# SCH_pipicoshield_2023-05-22.net
KiCad netlist of a schematic drawn in EasyEDA
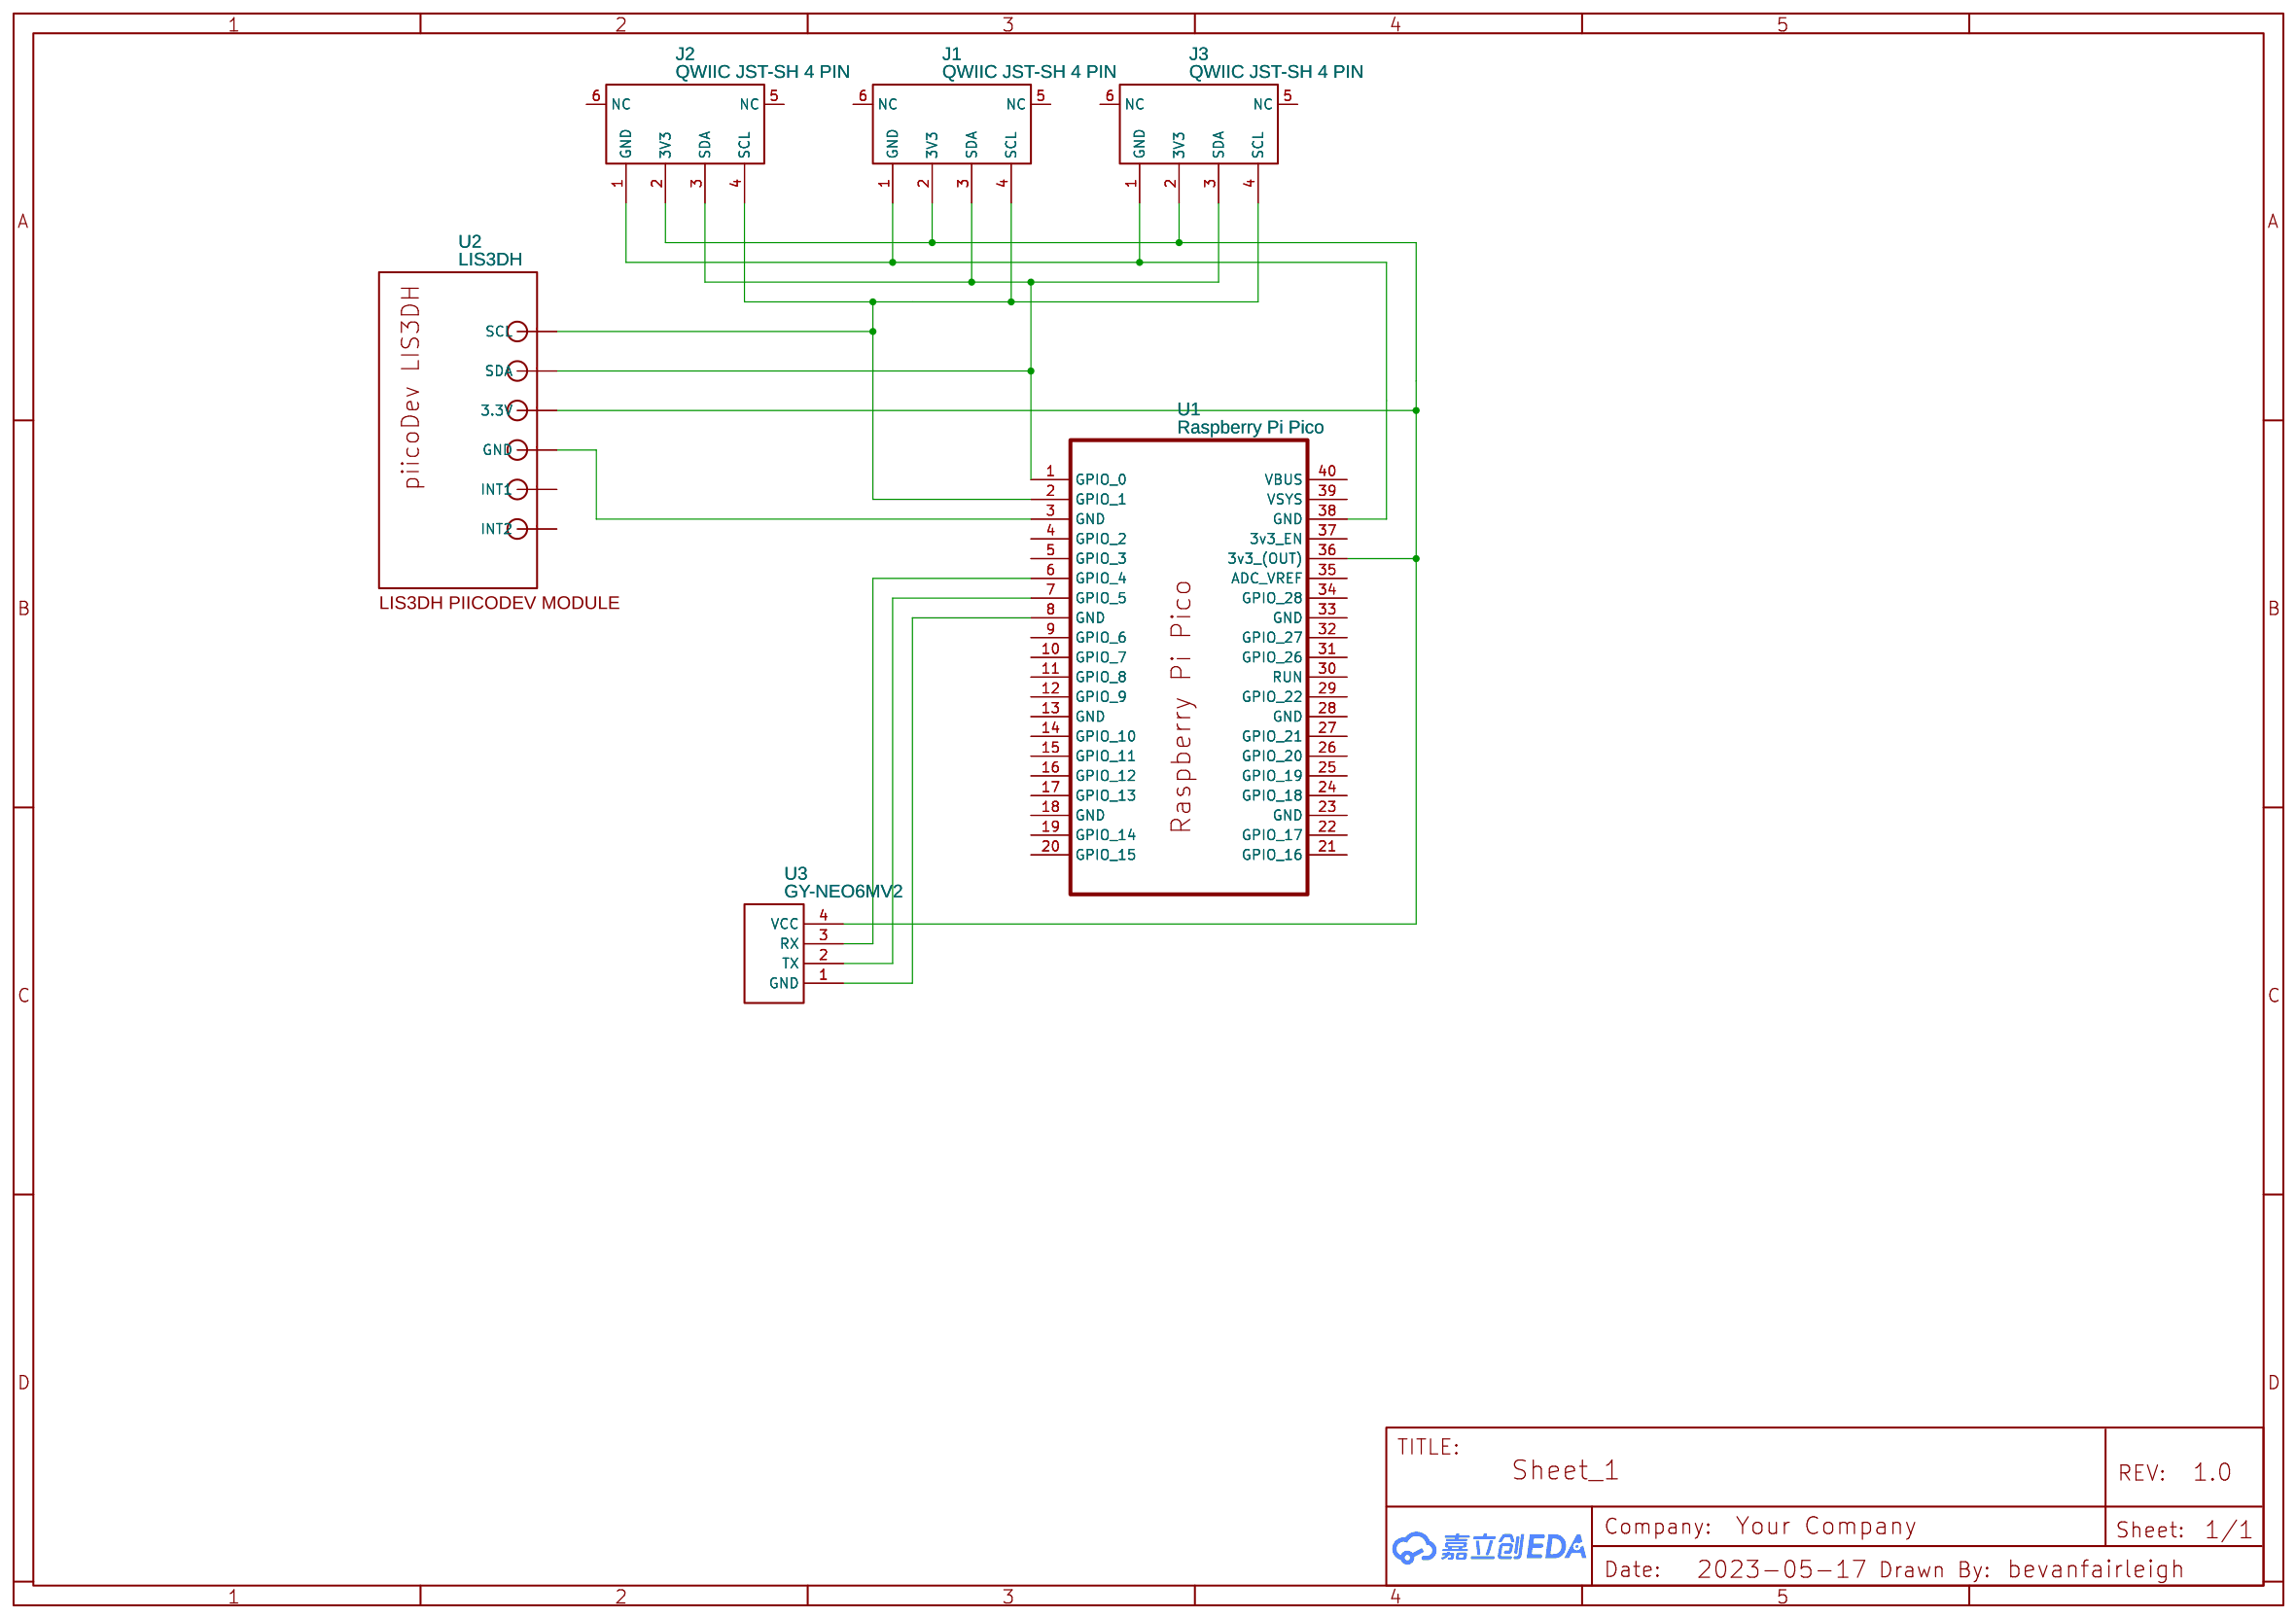
[diagram p0: schematic sheet]

(export (version "E")
  (design (tool "Eeschema 10.0.6"))
  (components
    (comp (ref "J1") (value "QWIIC JST-SH 4 PIN") (libsource (lib "") (part "QWIIC JST-SH 4 PIN")))
    (comp (ref "J2") (value "QWIIC JST-SH 4 PIN") (libsource (lib "") (part "QWIIC JST-SH 4 PIN")))
    (comp (ref "J3") (value "QWIIC JST-SH 4 PIN") (libsource (lib "") (part "QWIIC JST-SH 4 PIN")))
    (comp (ref "U1") (value "Raspberry Pi Pico") (libsource (lib "") (part "Raspberry Pi Pico W")))
    (comp (ref "U2") (value "LIS3DH") (libsource (lib "") (part "BME280")))
    (comp (ref "U3") (value "GY-NEO6MV2") (libsource (lib "") (part "GY-NEO6MV2")))
  )
  (nets
    (net (code "1") (name "Net-(J1-3V3)") (class "Default")
      (node (ref "J1") (pin "2") (pinfunction "3V3_2") (pintype "passive"))
      (node (ref "J2") (pin "2") (pinfunction "3V3_2") (pintype "passive"))
      (node (ref "J3") (pin "2") (pinfunction "3V3_2") (pintype "passive"))
      (node (ref "U1") (pin "36") (pinfunction "3v3_(OUT)_36") (pintype "unspecified"))
      (node (ref "U2") (pin "4") (pinfunction "3.3V_4") (pintype "unspecified"))
      (node (ref "U3") (pin "4") (pinfunction "VCC_4") (pintype "passive"))
    )
    (net (code "2") (name "Net-(J1-GND)") (class "Default")
      (node (ref "J1") (pin "1") (pinfunction "GND_1") (pintype "passive"))
      (node (ref "J2") (pin "1") (pinfunction "GND_1") (pintype "passive"))
      (node (ref "J3") (pin "1") (pinfunction "GND_1") (pintype "passive"))
      (node (ref "U1") (pin "38") (pinfunction "GND_38") (pintype "unspecified"))
    )
    (net (code "3") (name "Net-(J1-SCL)") (class "Default")
      (node (ref "J1") (pin "4") (pinfunction "SCL_4") (pintype "bidirectional"))
      (node (ref "J2") (pin "4") (pinfunction "SCL_4") (pintype "bidirectional"))
      (node (ref "J3") (pin "4") (pinfunction "SCL_4") (pintype "bidirectional"))
      (node (ref "U1") (pin "2") (pinfunction "GPIO_1_2") (pintype "unspecified"))
      (node (ref "U2") (pin "6") (pinfunction "SCL_6") (pintype "unspecified"))
    )
    (net (code "4") (name "Net-(J1-SDA)") (class "Default")
      (node (ref "J1") (pin "3") (pinfunction "SDA_3") (pintype "bidirectional"))
      (node (ref "J2") (pin "3") (pinfunction "SDA_3") (pintype "bidirectional"))
      (node (ref "J3") (pin "3") (pinfunction "SDA_3") (pintype "bidirectional"))
      (node (ref "U1") (pin "1") (pinfunction "GPIO_0_1") (pintype "unspecified"))
      (node (ref "U2") (pin "5") (pinfunction "SDA_5") (pintype "unspecified"))
    )
    (net (code "5") (name "Net-(U1-GPIO_4)") (class "Default")
      (node (ref "U1") (pin "6") (pinfunction "GPIO_4_6") (pintype "unspecified"))
      (node (ref "U3") (pin "3") (pinfunction "RX_3") (pintype "input"))
    )
    (net (code "6") (name "Net-(U1-GPIO_5)") (class "Default")
      (node (ref "U1") (pin "7") (pinfunction "GPIO_5_7") (pintype "unspecified"))
      (node (ref "U3") (pin "2") (pinfunction "TX_2") (pintype "output"))
    )
    (net (code "7") (name "Net-(U2-GND)") (class "Default")
      (node (ref "U1") (pin "3") (pinfunction "GND_3") (pintype "unspecified"))
      (node (ref "U2") (pin "3") (pinfunction "GND_3") (pintype "unspecified"))
    )
    (net (code "8") (name "Net-(U3-GND)") (class "Default")
      (node (ref "U1") (pin "8") (pinfunction "GND_8") (pintype "unspecified"))
      (node (ref "U3") (pin "1") (pinfunction "GND_1") (pintype "passive"))
    )
    (net (code "9") (name "unconnected-(J1-NC-Pad5)") (class "Default")
      (node (ref "J1") (pin "5") (pinfunction "NC_5") (pintype "unspecified"))
    )
    (net (code "10") (name "unconnected-(J1-NC-Pad6)") (class "Default")
      (node (ref "J1") (pin "6") (pinfunction "NC_6") (pintype "unspecified"))
    )
    (net (code "11") (name "unconnected-(J2-NC-Pad5)") (class "Default")
      (node (ref "J2") (pin "5") (pinfunction "NC_5") (pintype "unspecified"))
    )
    (net (code "12") (name "unconnected-(J2-NC-Pad6)") (class "Default")
      (node (ref "J2") (pin "6") (pinfunction "NC_6") (pintype "unspecified"))
    )
    (net (code "13") (name "unconnected-(J3-NC-Pad5)") (class "Default")
      (node (ref "J3") (pin "5") (pinfunction "NC_5") (pintype "unspecified"))
    )
    (net (code "14") (name "unconnected-(J3-NC-Pad6)") (class "Default")
      (node (ref "J3") (pin "6") (pinfunction "NC_6") (pintype "unspecified"))
    )
    (net (code "15") (name "unconnected-(U1-3v3_EN-Pad37)") (class "Default")
      (node (ref "U1") (pin "37") (pinfunction "3v3_EN_37") (pintype "unspecified"))
    )
    (net (code "16") (name "unconnected-(U1-ADC_VREF-Pad35)") (class "Default")
      (node (ref "U1") (pin "35") (pinfunction "ADC_VREF_35") (pintype "unspecified"))
    )
    (net (code "17") (name "unconnected-(U1-GND-Pad13)") (class "Default")
      (node (ref "U1") (pin "13") (pinfunction "GND_13") (pintype "unspecified"))
    )
    (net (code "18") (name "unconnected-(U1-GND-Pad18)") (class "Default")
      (node (ref "U1") (pin "18") (pinfunction "GND_18") (pintype "unspecified"))
    )
    (net (code "19") (name "unconnected-(U1-GND-Pad23)") (class "Default")
      (node (ref "U1") (pin "23") (pinfunction "GND_23") (pintype "unspecified"))
    )
    (net (code "20") (name "unconnected-(U1-GND-Pad28)") (class "Default")
      (node (ref "U1") (pin "28") (pinfunction "GND_28") (pintype "unspecified"))
    )
    (net (code "21") (name "unconnected-(U1-GND-Pad33)") (class "Default")
      (node (ref "U1") (pin "33") (pinfunction "GND_33") (pintype "unspecified"))
    )
    (net (code "22") (name "unconnected-(U1-GPIO_2-Pad4)") (class "Default")
      (node (ref "U1") (pin "4") (pinfunction "GPIO_2_4") (pintype "unspecified"))
    )
    (net (code "23") (name "unconnected-(U1-GPIO_3-Pad5)") (class "Default")
      (node (ref "U1") (pin "5") (pinfunction "GPIO_3_5") (pintype "unspecified"))
    )
    (net (code "24") (name "unconnected-(U1-GPIO_6-Pad9)") (class "Default")
      (node (ref "U1") (pin "9") (pinfunction "GPIO_6_9") (pintype "unspecified"))
    )
    (net (code "25") (name "unconnected-(U1-GPIO_7-Pad10)") (class "Default")
      (node (ref "U1") (pin "10") (pinfunction "GPIO_7_10") (pintype "unspecified"))
    )
    (net (code "26") (name "unconnected-(U1-GPIO_8-Pad11)") (class "Default")
      (node (ref "U1") (pin "11") (pinfunction "GPIO_8_11") (pintype "unspecified"))
    )
    (net (code "27") (name "unconnected-(U1-GPIO_9-Pad12)") (class "Default")
      (node (ref "U1") (pin "12") (pinfunction "GPIO_9_12") (pintype "unspecified"))
    )
    (net (code "28") (name "unconnected-(U1-GPIO_10-Pad14)") (class "Default")
      (node (ref "U1") (pin "14") (pinfunction "GPIO_10_14") (pintype "unspecified"))
    )
    (net (code "29") (name "unconnected-(U1-GPIO_11-Pad15)") (class "Default")
      (node (ref "U1") (pin "15") (pinfunction "GPIO_11_15") (pintype "unspecified"))
    )
    (net (code "30") (name "unconnected-(U1-GPIO_12-Pad16)") (class "Default")
      (node (ref "U1") (pin "16") (pinfunction "GPIO_12_16") (pintype "unspecified"))
    )
    (net (code "31") (name "unconnected-(U1-GPIO_13-Pad17)") (class "Default")
      (node (ref "U1") (pin "17") (pinfunction "GPIO_13_17") (pintype "unspecified"))
    )
    (net (code "32") (name "unconnected-(U1-GPIO_14-Pad19)") (class "Default")
      (node (ref "U1") (pin "19") (pinfunction "GPIO_14_19") (pintype "unspecified"))
    )
    (net (code "33") (name "unconnected-(U1-GPIO_15-Pad20)") (class "Default")
      (node (ref "U1") (pin "20") (pinfunction "GPIO_15_20") (pintype "unspecified"))
    )
    (net (code "34") (name "unconnected-(U1-GPIO_16-Pad21)") (class "Default")
      (node (ref "U1") (pin "21") (pinfunction "GPIO_16_21") (pintype "unspecified"))
    )
    (net (code "35") (name "unconnected-(U1-GPIO_17-Pad22)") (class "Default")
      (node (ref "U1") (pin "22") (pinfunction "GPIO_17_22") (pintype "unspecified"))
    )
    (net (code "36") (name "unconnected-(U1-GPIO_18-Pad24)") (class "Default")
      (node (ref "U1") (pin "24") (pinfunction "GPIO_18_24") (pintype "unspecified"))
    )
    (net (code "37") (name "unconnected-(U1-GPIO_19-Pad25)") (class "Default")
      (node (ref "U1") (pin "25") (pinfunction "GPIO_19_25") (pintype "unspecified"))
    )
    (net (code "38") (name "unconnected-(U1-GPIO_20-Pad26)") (class "Default")
      (node (ref "U1") (pin "26") (pinfunction "GPIO_20_26") (pintype "unspecified"))
    )
    (net (code "39") (name "unconnected-(U1-GPIO_21-Pad27)") (class "Default")
      (node (ref "U1") (pin "27") (pinfunction "GPIO_21_27") (pintype "unspecified"))
    )
    (net (code "40") (name "unconnected-(U1-GPIO_22-Pad29)") (class "Default")
      (node (ref "U1") (pin "29") (pinfunction "GPIO_22_29") (pintype "unspecified"))
    )
    (net (code "41") (name "unconnected-(U1-GPIO_26-Pad31)") (class "Default")
      (node (ref "U1") (pin "31") (pinfunction "GPIO_26_31") (pintype "unspecified"))
    )
    (net (code "42") (name "unconnected-(U1-GPIO_27-Pad32)") (class "Default")
      (node (ref "U1") (pin "32") (pinfunction "GPIO_27_32") (pintype "unspecified"))
    )
    (net (code "43") (name "unconnected-(U1-GPIO_28-Pad34)") (class "Default")
      (node (ref "U1") (pin "34") (pinfunction "GPIO_28_34") (pintype "unspecified"))
    )
    (net (code "44") (name "unconnected-(U1-RUN-Pad30)") (class "Default")
      (node (ref "U1") (pin "30") (pinfunction "RUN_30") (pintype "unspecified"))
    )
    (net (code "45") (name "unconnected-(U1-VBUS-Pad40)") (class "Default")
      (node (ref "U1") (pin "40") (pinfunction "VBUS_40") (pintype "unspecified"))
    )
    (net (code "46") (name "unconnected-(U1-VSYS-Pad39)") (class "Default")
      (node (ref "U1") (pin "39") (pinfunction "VSYS_39") (pintype "unspecified"))
    )
    (net (code "47") (name "unconnected-(U2-INT1-Pad2)") (class "Default")
      (node (ref "U2") (pin "2") (pinfunction "INT1_2") (pintype "unspecified"))
    )
    (net (code "48") (name "unconnected-(U2-INT2-Pad1)") (class "Default")
      (node (ref "U2") (pin "1") (pinfunction "INT2_1") (pintype "unspecified"))
    )
  )
)
